# kilo.net
KiCad netlist of a schematic drawn in EAGLE
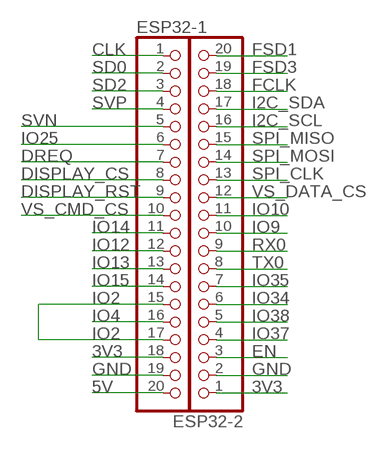
[diagram p0: schematic, sheet 1]
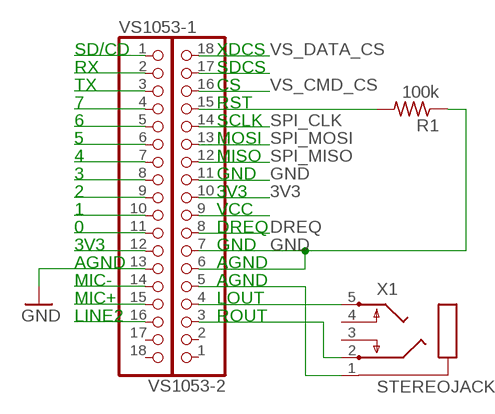
[diagram p1: schematic, sheet 2]
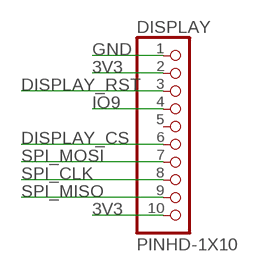
[diagram p2: schematic, sheet 3]
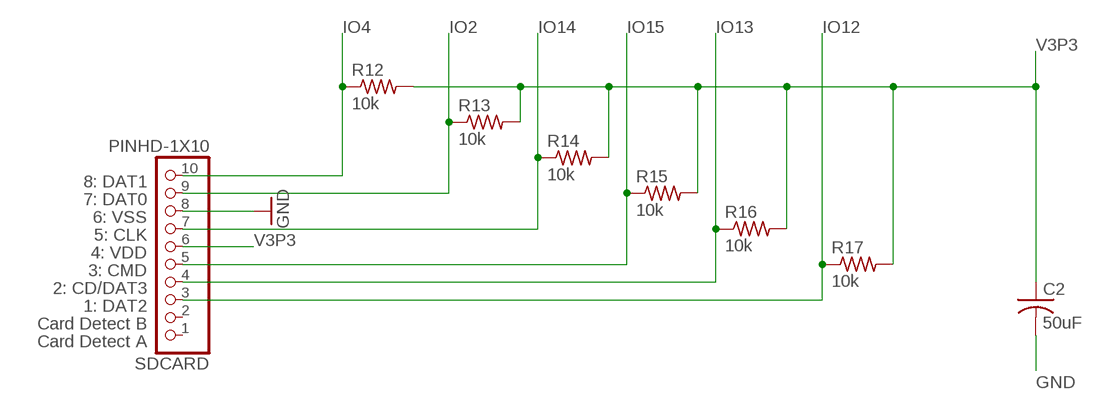
[diagram p3: schematic, sheet 4]
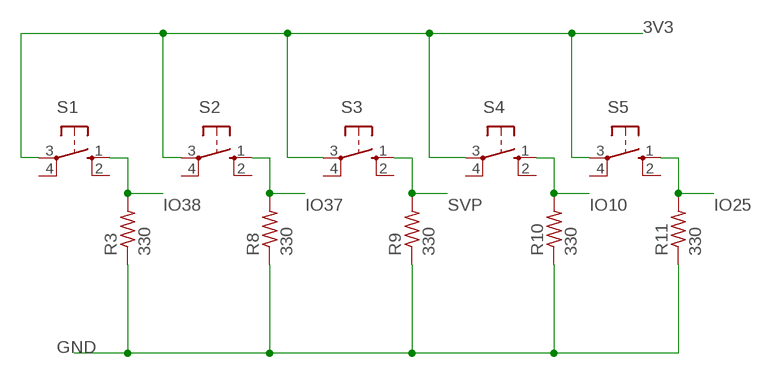
[diagram p4: schematic, sheet 5]

(export (version "E")
  (design (tool "Eeschema 10.0.6"))
  (components
    (comp (ref "ESP32-1")
      (value "PINHD-1X20")
      (footprint "eagle-import:1X20")
      (libsource (lib "eagle-import") (part "PINHD-1X20"))
    )
    (comp (ref "ESP32-2")
      (value "PINHD-1X20")
      (footprint "eagle-import:1X20")
      (libsource (lib "eagle-import") (part "PINHD-1X20"))
    )
    (comp (ref "C2")
      (value "50uF")
      (footprint "eagle-import:C025-024X044")
      (libsource (lib "eagle-import") (part "C-US025-024X044"))
    )
    (comp (ref "R12")
      (value "10k")
      (footprint "eagle-import:0204V")
      (libsource (lib "eagle-import") (part "R-US_0204/2V"))
    )
    (comp (ref "R13")
      (value "10k")
      (footprint "eagle-import:0204V")
      (libsource (lib "eagle-import") (part "R-US_0204/2V"))
    )
    (comp (ref "R14")
      (value "10k")
      (footprint "eagle-import:0204V")
      (libsource (lib "eagle-import") (part "R-US_0204/2V"))
    )
    (comp (ref "R15")
      (value "10k")
      (footprint "eagle-import:0204V")
      (libsource (lib "eagle-import") (part "R-US_0204/2V"))
    )
    (comp (ref "R16")
      (value "10k")
      (footprint "eagle-import:0204V")
      (libsource (lib "eagle-import") (part "R-US_0204/2V"))
    )
    (comp (ref "R17")
      (value "10k")
      (footprint "eagle-import:0204V")
      (libsource (lib "eagle-import") (part "R-US_0204/2V"))
    )
    (comp (ref "SDCARD")
      (value "PINHD-1X10")
      (footprint "eagle-import:1X10-BIG")
      (libsource (lib "eagle-import") (part "PINHD-1X10"))
    )
    (comp (ref "R1")
      (value "100k")
      (footprint "eagle-import:0204V")
      (libsource (lib "eagle-import") (part "R-US_0204/2V"))
    )
    (comp (ref "VS1053-1")
      (value "PINHD-1X18")
      (footprint "eagle-import:1X18")
      (libsource (lib "eagle-import") (part "PINHD-1X18"))
    )
    (comp (ref "VS1053-2")
      (value "PINHD-1X18")
      (footprint "eagle-import:1X18")
      (libsource (lib "eagle-import") (part "PINHD-1X18"))
    )
    (comp (ref "X1")
      (value "STEREOJACK")
      (footprint "eagle-import:STX3100")
      (libsource (lib "eagle-import") (part "STEREOJACK"))
    )
    (comp (ref "DISPLAY")
      (value "PINHD-1X10")
      (footprint "eagle-import:1X10-BIG")
      (libsource (lib "eagle-import") (part "PINHD-1X10"))
    )
    (comp (ref "R3")
      (value "330")
      (footprint "eagle-import:0204V")
      (libsource (lib "eagle-import") (part "R-US_0204/2V"))
    )
    (comp (ref "R8")
      (value "330")
      (footprint "eagle-import:0204V")
      (libsource (lib "eagle-import") (part "R-US_0204/2V"))
    )
    (comp (ref "R9")
      (value "330")
      (footprint "eagle-import:0204V")
      (libsource (lib "eagle-import") (part "R-US_0204/2V"))
    )
    (comp (ref "R10")
      (value "330")
      (footprint "eagle-import:0204V")
      (libsource (lib "eagle-import") (part "R-US_0204/2V"))
    )
    (comp (ref "R11")
      (value "330")
      (footprint "eagle-import:0204V")
      (libsource (lib "eagle-import") (part "R-US_0204/2V"))
    )
    (comp (ref "S1")
      (value "10-XX")
      (footprint "eagle-import:B3F-10XX")
      (fields (field (name "MPN") "B3F-1000"))
      (libsource (lib "eagle-import") (part "10-XX"))
    )
    (comp (ref "S2")
      (value "10-XX")
      (footprint "eagle-import:B3F-10XX")
      (fields (field (name "MPN") "B3F-1000"))
      (libsource (lib "eagle-import") (part "10-XX"))
    )
    (comp (ref "S3")
      (value "10-XX")
      (footprint "eagle-import:B3F-10XX")
      (fields (field (name "MPN") "B3F-1000"))
      (libsource (lib "eagle-import") (part "10-XX"))
    )
    (comp (ref "S4")
      (value "10-XX")
      (footprint "eagle-import:B3F-10XX")
      (fields (field (name "MPN") "B3F-1000"))
      (libsource (lib "eagle-import") (part "10-XX"))
    )
    (comp (ref "S5")
      (value "10-XX")
      (footprint "eagle-import:B3F-10XX")
      (fields (field (name "MPN") "B3F-1000"))
      (libsource (lib "eagle-import") (part "10-XX"))
    )
  )
  (nets
    (net (code "1") (name "3V3") (class "Default")
      (node (ref "DISPLAY") (pin "10") (pinfunction "10_10") (pintype "passive"))
      (node (ref "DISPLAY") (pin "2") (pinfunction "2_2") (pintype "passive"))
      (node (ref "ESP32-1") (pin "18") (pinfunction "18_18") (pintype "passive"))
      (node (ref "ESP32-2") (pin "1") (pinfunction "1_1") (pintype "passive"))
      (node (ref "S1") (pin "3") (pinfunction "P_3") (pintype "passive"))
      (node (ref "S2") (pin "3") (pinfunction "P_3") (pintype "passive"))
      (node (ref "S3") (pin "3") (pinfunction "P_3") (pintype "passive"))
      (node (ref "S4") (pin "3") (pinfunction "P_3") (pintype "passive"))
      (node (ref "S5") (pin "3") (pinfunction "P_3") (pintype "passive"))
      (node (ref "VS1053-2") (pin "10") (pinfunction "10_10") (pintype "passive"))
    )
    (net (code "2") (name "5V") (class "Default")
      (node (ref "ESP32-1") (pin "20") (pinfunction "20_20") (pintype "passive"))
    )
    (net (code "3") (name "CLK") (class "Default")
      (node (ref "ESP32-1") (pin "1") (pinfunction "1_1") (pintype "passive"))
    )
    (net (code "4") (name "DISPLAY_CS") (class "Default")
      (node (ref "DISPLAY") (pin "6") (pinfunction "6_6") (pintype "passive"))
      (node (ref "ESP32-1") (pin "8") (pinfunction "8_8") (pintype "passive"))
    )
    (net (code "5") (name "DISPLAY_RST") (class "Default")
      (node (ref "DISPLAY") (pin "3") (pinfunction "3_3") (pintype "passive"))
      (node (ref "ESP32-1") (pin "9") (pinfunction "9_9") (pintype "passive"))
    )
    (net (code "6") (name "DREQ") (class "Default")
      (node (ref "ESP32-1") (pin "7") (pinfunction "7_7") (pintype "passive"))
      (node (ref "VS1053-2") (pin "8") (pinfunction "8_8") (pintype "passive"))
    )
    (net (code "7") (name "EN") (class "Default")
      (node (ref "ESP32-2") (pin "3") (pinfunction "3_3") (pintype "passive"))
    )
    (net (code "8") (name "FCLK") (class "Default")
      (node (ref "ESP32-2") (pin "18") (pinfunction "18_18") (pintype "passive"))
    )
    (net (code "9") (name "FSD1") (class "Default")
      (node (ref "ESP32-2") (pin "20") (pinfunction "20_20") (pintype "passive"))
    )
    (net (code "10") (name "FSD3") (class "Default")
      (node (ref "ESP32-2") (pin "19") (pinfunction "19_19") (pintype "passive"))
    )
    (net (code "11") (name "GND") (class "Default")
      (node (ref "C2") (pin "2") (pinfunction "2_2") (pintype "passive"))
      (node (ref "DISPLAY") (pin "1") (pinfunction "1_1") (pintype "passive"))
      (node (ref "ESP32-1") (pin "19") (pinfunction "19_19") (pintype "passive"))
      (node (ref "ESP32-2") (pin "2") (pinfunction "2_2") (pintype "passive"))
      (node (ref "R1") (pin "1") (pinfunction "1_1") (pintype "passive"))
      (node (ref "R10") (pin "1") (pinfunction "1_1") (pintype "passive"))
      (node (ref "R11") (pin "1") (pinfunction "1_1") (pintype "passive"))
      (node (ref "R3") (pin "1") (pinfunction "1_1") (pintype "passive"))
      (node (ref "R8") (pin "1") (pinfunction "1_1") (pintype "passive"))
      (node (ref "R9") (pin "1") (pinfunction "1_1") (pintype "passive"))
      (node (ref "SDCARD") (pin "8") (pinfunction "8_8") (pintype "passive"))
      (node (ref "VS1053-1") (pin "13") (pinfunction "13_13") (pintype "passive"))
      (node (ref "VS1053-2") (pin "11") (pinfunction "11_11") (pintype "passive"))
      (node (ref "VS1053-2") (pin "6") (pinfunction "6_6") (pintype "passive"))
      (node (ref "VS1053-2") (pin "7") (pinfunction "7_7") (pintype "passive"))
    )
    (net (code "12") (name "I2C_SCL") (class "Default")
      (node (ref "ESP32-2") (pin "16") (pinfunction "16_16") (pintype "passive"))
    )
    (net (code "13") (name "I2C_SDA") (class "Default")
      (node (ref "ESP32-2") (pin "17") (pinfunction "17_17") (pintype "passive"))
    )
    (net (code "14") (name "IO2") (class "Default")
      (node (ref "ESP32-1") (pin "15") (pinfunction "15_15") (pintype "passive"))
      (node (ref "ESP32-1") (pin "17") (pinfunction "17_17") (pintype "passive"))
      (node (ref "R13") (pin "1") (pinfunction "1_1") (pintype "passive"))
      (node (ref "SDCARD") (pin "9") (pinfunction "9_9") (pintype "passive"))
    )
    (net (code "15") (name "IO4") (class "Default")
      (node (ref "ESP32-1") (pin "16") (pinfunction "16_16") (pintype "passive"))
      (node (ref "R12") (pin "1") (pinfunction "1_1") (pintype "passive"))
      (node (ref "SDCARD") (pin "10") (pinfunction "10_10") (pintype "passive"))
    )
    (net (code "16") (name "IO9") (class "Default")
      (node (ref "DISPLAY") (pin "4") (pinfunction "4_4") (pintype "passive"))
      (node (ref "ESP32-2") (pin "10") (pinfunction "10_10") (pintype "passive"))
    )
    (net (code "17") (name "IO10") (class "Default")
      (node (ref "ESP32-2") (pin "11") (pinfunction "11_11") (pintype "passive"))
      (node (ref "R10") (pin "2") (pinfunction "2_2") (pintype "passive"))
      (node (ref "S4") (pin "1") (pinfunction "S_1") (pintype "passive"))
    )
    (net (code "18") (name "IO12") (class "Default")
      (node (ref "ESP32-1") (pin "12") (pinfunction "12_12") (pintype "passive"))
      (node (ref "R17") (pin "1") (pinfunction "1_1") (pintype "passive"))
      (node (ref "SDCARD") (pin "3") (pinfunction "3_3") (pintype "passive"))
    )
    (net (code "19") (name "IO13") (class "Default")
      (node (ref "ESP32-1") (pin "13") (pinfunction "13_13") (pintype "passive"))
      (node (ref "R16") (pin "1") (pinfunction "1_1") (pintype "passive"))
      (node (ref "SDCARD") (pin "4") (pinfunction "4_4") (pintype "passive"))
    )
    (net (code "20") (name "IO14") (class "Default")
      (node (ref "ESP32-1") (pin "11") (pinfunction "11_11") (pintype "passive"))
      (node (ref "R14") (pin "1") (pinfunction "1_1") (pintype "passive"))
      (node (ref "SDCARD") (pin "7") (pinfunction "7_7") (pintype "passive"))
    )
    (net (code "21") (name "IO15") (class "Default")
      (node (ref "ESP32-1") (pin "14") (pinfunction "14_14") (pintype "passive"))
      (node (ref "R15") (pin "1") (pinfunction "1_1") (pintype "passive"))
      (node (ref "SDCARD") (pin "5") (pinfunction "5_5") (pintype "passive"))
    )
    (net (code "22") (name "IO25") (class "Default")
      (node (ref "ESP32-1") (pin "6") (pinfunction "6_6") (pintype "passive"))
      (node (ref "R11") (pin "2") (pinfunction "2_2") (pintype "passive"))
      (node (ref "S5") (pin "1") (pinfunction "S_1") (pintype "passive"))
    )
    (net (code "23") (name "IO34") (class "Default")
      (node (ref "ESP32-2") (pin "6") (pinfunction "6_6") (pintype "passive"))
    )
    (net (code "24") (name "IO35") (class "Default")
      (node (ref "ESP32-2") (pin "7") (pinfunction "7_7") (pintype "passive"))
    )
    (net (code "25") (name "IO37") (class "Default")
      (node (ref "ESP32-2") (pin "4") (pinfunction "4_4") (pintype "passive"))
      (node (ref "R8") (pin "2") (pinfunction "2_2") (pintype "passive"))
      (node (ref "S2") (pin "1") (pinfunction "S_1") (pintype "passive"))
    )
    (net (code "26") (name "IO38") (class "Default")
      (node (ref "ESP32-2") (pin "5") (pinfunction "5_5") (pintype "passive"))
      (node (ref "R3") (pin "2") (pinfunction "2_2") (pintype "passive"))
      (node (ref "S1") (pin "1") (pinfunction "S_1") (pintype "passive"))
    )
    (net (code "27") (name "Net-(R1-Pad2)") (class "Default")
      (node (ref "R1") (pin "2") (pinfunction "2_2") (pintype "passive"))
      (node (ref "VS1053-2") (pin "15") (pinfunction "15_15") (pintype "passive"))
    )
    (net (code "28") (name "Net-(VS1053-2-Pad3)") (class "Default")
      (node (ref "VS1053-2") (pin "3") (pinfunction "3_3") (pintype "passive"))
      (node (ref "X1") (pin "2") (pinfunction "2_2") (pintype "passive"))
    )
    (net (code "29") (name "Net-(VS1053-2-Pad4)") (class "Default")
      (node (ref "VS1053-2") (pin "4") (pinfunction "4_4") (pintype "passive"))
      (node (ref "X1") (pin "5") (pinfunction "5_5") (pintype "passive"))
    )
    (net (code "30") (name "Net-(VS1053-2-Pad5)") (class "Default")
      (node (ref "VS1053-2") (pin "5") (pinfunction "5_5") (pintype "passive"))
      (node (ref "X1") (pin "1") (pinfunction "1_1") (pintype "passive"))
    )
    (net (code "31") (name "RX0") (class "Default")
      (node (ref "ESP32-2") (pin "9") (pinfunction "9_9") (pintype "passive"))
    )
    (net (code "32") (name "SD0") (class "Default")
      (node (ref "ESP32-1") (pin "2") (pinfunction "2_2") (pintype "passive"))
    )
    (net (code "33") (name "SD2") (class "Default")
      (node (ref "ESP32-1") (pin "3") (pinfunction "3_3") (pintype "passive"))
    )
    (net (code "34") (name "SPI_CLK") (class "Default")
      (node (ref "DISPLAY") (pin "8") (pinfunction "8_8") (pintype "passive"))
      (node (ref "ESP32-2") (pin "13") (pinfunction "13_13") (pintype "passive"))
      (node (ref "VS1053-2") (pin "14") (pinfunction "14_14") (pintype "passive"))
    )
    (net (code "35") (name "SPI_MISO") (class "Default")
      (node (ref "DISPLAY") (pin "9") (pinfunction "9_9") (pintype "passive"))
      (node (ref "ESP32-2") (pin "15") (pinfunction "15_15") (pintype "passive"))
      (node (ref "VS1053-2") (pin "12") (pinfunction "12_12") (pintype "passive"))
    )
    (net (code "36") (name "SPI_MOSI") (class "Default")
      (node (ref "DISPLAY") (pin "7") (pinfunction "7_7") (pintype "passive"))
      (node (ref "ESP32-2") (pin "14") (pinfunction "14_14") (pintype "passive"))
      (node (ref "VS1053-2") (pin "13") (pinfunction "13_13") (pintype "passive"))
    )
    (net (code "37") (name "SVN") (class "Default")
      (node (ref "ESP32-1") (pin "5") (pinfunction "5_5") (pintype "passive"))
    )
    (net (code "38") (name "SVP") (class "Default")
      (node (ref "ESP32-1") (pin "4") (pinfunction "4_4") (pintype "passive"))
      (node (ref "R9") (pin "2") (pinfunction "2_2") (pintype "passive"))
      (node (ref "S3") (pin "1") (pinfunction "S_1") (pintype "passive"))
    )
    (net (code "39") (name "TX0") (class "Default")
      (node (ref "ESP32-2") (pin "8") (pinfunction "8_8") (pintype "passive"))
    )
    (net (code "40") (name "V3P3") (class "Default")
      (node (ref "C2") (pin "1") (pinfunction "1_1") (pintype "passive"))
      (node (ref "R12") (pin "2") (pinfunction "2_2") (pintype "passive"))
      (node (ref "R13") (pin "2") (pinfunction "2_2") (pintype "passive"))
      (node (ref "R14") (pin "2") (pinfunction "2_2") (pintype "passive"))
      (node (ref "R15") (pin "2") (pinfunction "2_2") (pintype "passive"))
      (node (ref "R16") (pin "2") (pinfunction "2_2") (pintype "passive"))
      (node (ref "R17") (pin "2") (pinfunction "2_2") (pintype "passive"))
      (node (ref "SDCARD") (pin "6") (pinfunction "6_6") (pintype "passive"))
    )
    (net (code "41") (name "VS_CMD_CS") (class "Default")
      (node (ref "ESP32-1") (pin "10") (pinfunction "10_10") (pintype "passive"))
      (node (ref "VS1053-2") (pin "16") (pinfunction "16_16") (pintype "passive"))
    )
    (net (code "42") (name "VS_DATA_CS") (class "Default")
      (node (ref "ESP32-2") (pin "12") (pinfunction "12_12") (pintype "passive"))
      (node (ref "VS1053-2") (pin "18") (pinfunction "18_18") (pintype "passive"))
    )
    (net (code "43") (name "unconnected-(DISPLAY-Pad5)") (class "Default")
      (node (ref "DISPLAY") (pin "5") (pinfunction "5_5") (pintype "passive"))
    )
    (net (code "44") (name "unconnected-(S1-P1-Pad4)") (class "Default")
      (node (ref "S1") (pin "4") (pinfunction "P1_4") (pintype "passive"))
    )
    (net (code "45") (name "unconnected-(S1-S1-Pad2)") (class "Default")
      (node (ref "S1") (pin "2") (pinfunction "S1_2") (pintype "passive"))
    )
    (net (code "46") (name "unconnected-(S2-P1-Pad4)") (class "Default")
      (node (ref "S2") (pin "4") (pinfunction "P1_4") (pintype "passive"))
    )
    (net (code "47") (name "unconnected-(S2-S1-Pad2)") (class "Default")
      (node (ref "S2") (pin "2") (pinfunction "S1_2") (pintype "passive"))
    )
    (net (code "48") (name "unconnected-(S3-P1-Pad4)") (class "Default")
      (node (ref "S3") (pin "4") (pinfunction "P1_4") (pintype "passive"))
    )
    (net (code "49") (name "unconnected-(S3-S1-Pad2)") (class "Default")
      (node (ref "S3") (pin "2") (pinfunction "S1_2") (pintype "passive"))
    )
    (net (code "50") (name "unconnected-(S4-P1-Pad4)") (class "Default")
      (node (ref "S4") (pin "4") (pinfunction "P1_4") (pintype "passive"))
    )
    (net (code "51") (name "unconnected-(S4-S1-Pad2)") (class "Default")
      (node (ref "S4") (pin "2") (pinfunction "S1_2") (pintype "passive"))
    )
    (net (code "52") (name "unconnected-(S5-P1-Pad4)") (class "Default")
      (node (ref "S5") (pin "4") (pinfunction "P1_4") (pintype "passive"))
    )
    (net (code "53") (name "unconnected-(S5-S1-Pad2)") (class "Default")
      (node (ref "S5") (pin "2") (pinfunction "S1_2") (pintype "passive"))
    )
    (net (code "54") (name "unconnected-(SDCARD-Pad1)") (class "Default")
      (node (ref "SDCARD") (pin "1") (pinfunction "1_1") (pintype "passive"))
    )
    (net (code "55") (name "unconnected-(SDCARD-Pad2)") (class "Default")
      (node (ref "SDCARD") (pin "2") (pinfunction "2_2") (pintype "passive"))
    )
    (net (code "56") (name "unconnected-(VS1053-1-Pad1)") (class "Default")
      (node (ref "VS1053-1") (pin "1") (pinfunction "1_1") (pintype "passive"))
    )
    (net (code "57") (name "unconnected-(VS1053-1-Pad2)") (class "Default")
      (node (ref "VS1053-1") (pin "2") (pinfunction "2_2") (pintype "passive"))
    )
    (net (code "58") (name "unconnected-(VS1053-1-Pad3)") (class "Default")
      (node (ref "VS1053-1") (pin "3") (pinfunction "3_3") (pintype "passive"))
    )
    (net (code "59") (name "unconnected-(VS1053-1-Pad4)") (class "Default")
      (node (ref "VS1053-1") (pin "4") (pinfunction "4_4") (pintype "passive"))
    )
    (net (code "60") (name "unconnected-(VS1053-1-Pad5)") (class "Default")
      (node (ref "VS1053-1") (pin "5") (pinfunction "5_5") (pintype "passive"))
    )
    (net (code "61") (name "unconnected-(VS1053-1-Pad6)") (class "Default")
      (node (ref "VS1053-1") (pin "6") (pinfunction "6_6") (pintype "passive"))
    )
    (net (code "62") (name "unconnected-(VS1053-1-Pad7)") (class "Default")
      (node (ref "VS1053-1") (pin "7") (pinfunction "7_7") (pintype "passive"))
    )
    (net (code "63") (name "unconnected-(VS1053-1-Pad8)") (class "Default")
      (node (ref "VS1053-1") (pin "8") (pinfunction "8_8") (pintype "passive"))
    )
    (net (code "64") (name "unconnected-(VS1053-1-Pad9)") (class "Default")
      (node (ref "VS1053-1") (pin "9") (pinfunction "9_9") (pintype "passive"))
    )
    (net (code "65") (name "unconnected-(VS1053-1-Pad10)") (class "Default")
      (node (ref "VS1053-1") (pin "10") (pinfunction "10_10") (pintype "passive"))
    )
    (net (code "66") (name "unconnected-(VS1053-1-Pad11)") (class "Default")
      (node (ref "VS1053-1") (pin "11") (pinfunction "11_11") (pintype "passive"))
    )
    (net (code "67") (name "unconnected-(VS1053-1-Pad12)") (class "Default")
      (node (ref "VS1053-1") (pin "12") (pinfunction "12_12") (pintype "passive"))
    )
    (net (code "68") (name "unconnected-(VS1053-1-Pad14)") (class "Default")
      (node (ref "VS1053-1") (pin "14") (pinfunction "14_14") (pintype "passive"))
    )
    (net (code "69") (name "unconnected-(VS1053-1-Pad15)") (class "Default")
      (node (ref "VS1053-1") (pin "15") (pinfunction "15_15") (pintype "passive"))
    )
    (net (code "70") (name "unconnected-(VS1053-1-Pad16)") (class "Default")
      (node (ref "VS1053-1") (pin "16") (pinfunction "16_16") (pintype "passive"))
    )
    (net (code "71") (name "unconnected-(VS1053-1-Pad17)") (class "Default")
      (node (ref "VS1053-1") (pin "17") (pinfunction "17_17") (pintype "passive"))
    )
    (net (code "72") (name "unconnected-(VS1053-1-Pad18)") (class "Default")
      (node (ref "VS1053-1") (pin "18") (pinfunction "18_18") (pintype "passive"))
    )
    (net (code "73") (name "unconnected-(VS1053-2-Pad1)") (class "Default")
      (node (ref "VS1053-2") (pin "1") (pinfunction "1_1") (pintype "passive"))
    )
    (net (code "74") (name "unconnected-(VS1053-2-Pad2)") (class "Default")
      (node (ref "VS1053-2") (pin "2") (pinfunction "2_2") (pintype "passive"))
    )
    (net (code "75") (name "unconnected-(VS1053-2-Pad9)") (class "Default")
      (node (ref "VS1053-2") (pin "9") (pinfunction "9_9") (pintype "passive"))
    )
    (net (code "76") (name "unconnected-(VS1053-2-Pad17)") (class "Default")
      (node (ref "VS1053-2") (pin "17") (pinfunction "17_17") (pintype "passive"))
    )
    (net (code "77") (name "unconnected-(X1-Pad3)") (class "Default")
      (node (ref "X1") (pin "3") (pinfunction "3_3") (pintype "passive"))
    )
    (net (code "78") (name "unconnected-(X1-Pad4)") (class "Default")
      (node (ref "X1") (pin "4") (pinfunction "4_4") (pintype "passive"))
    )
  )
)
